# dcy_vca_v1_0_0.net
KiCad netlist of a schematic drawn in EAGLE
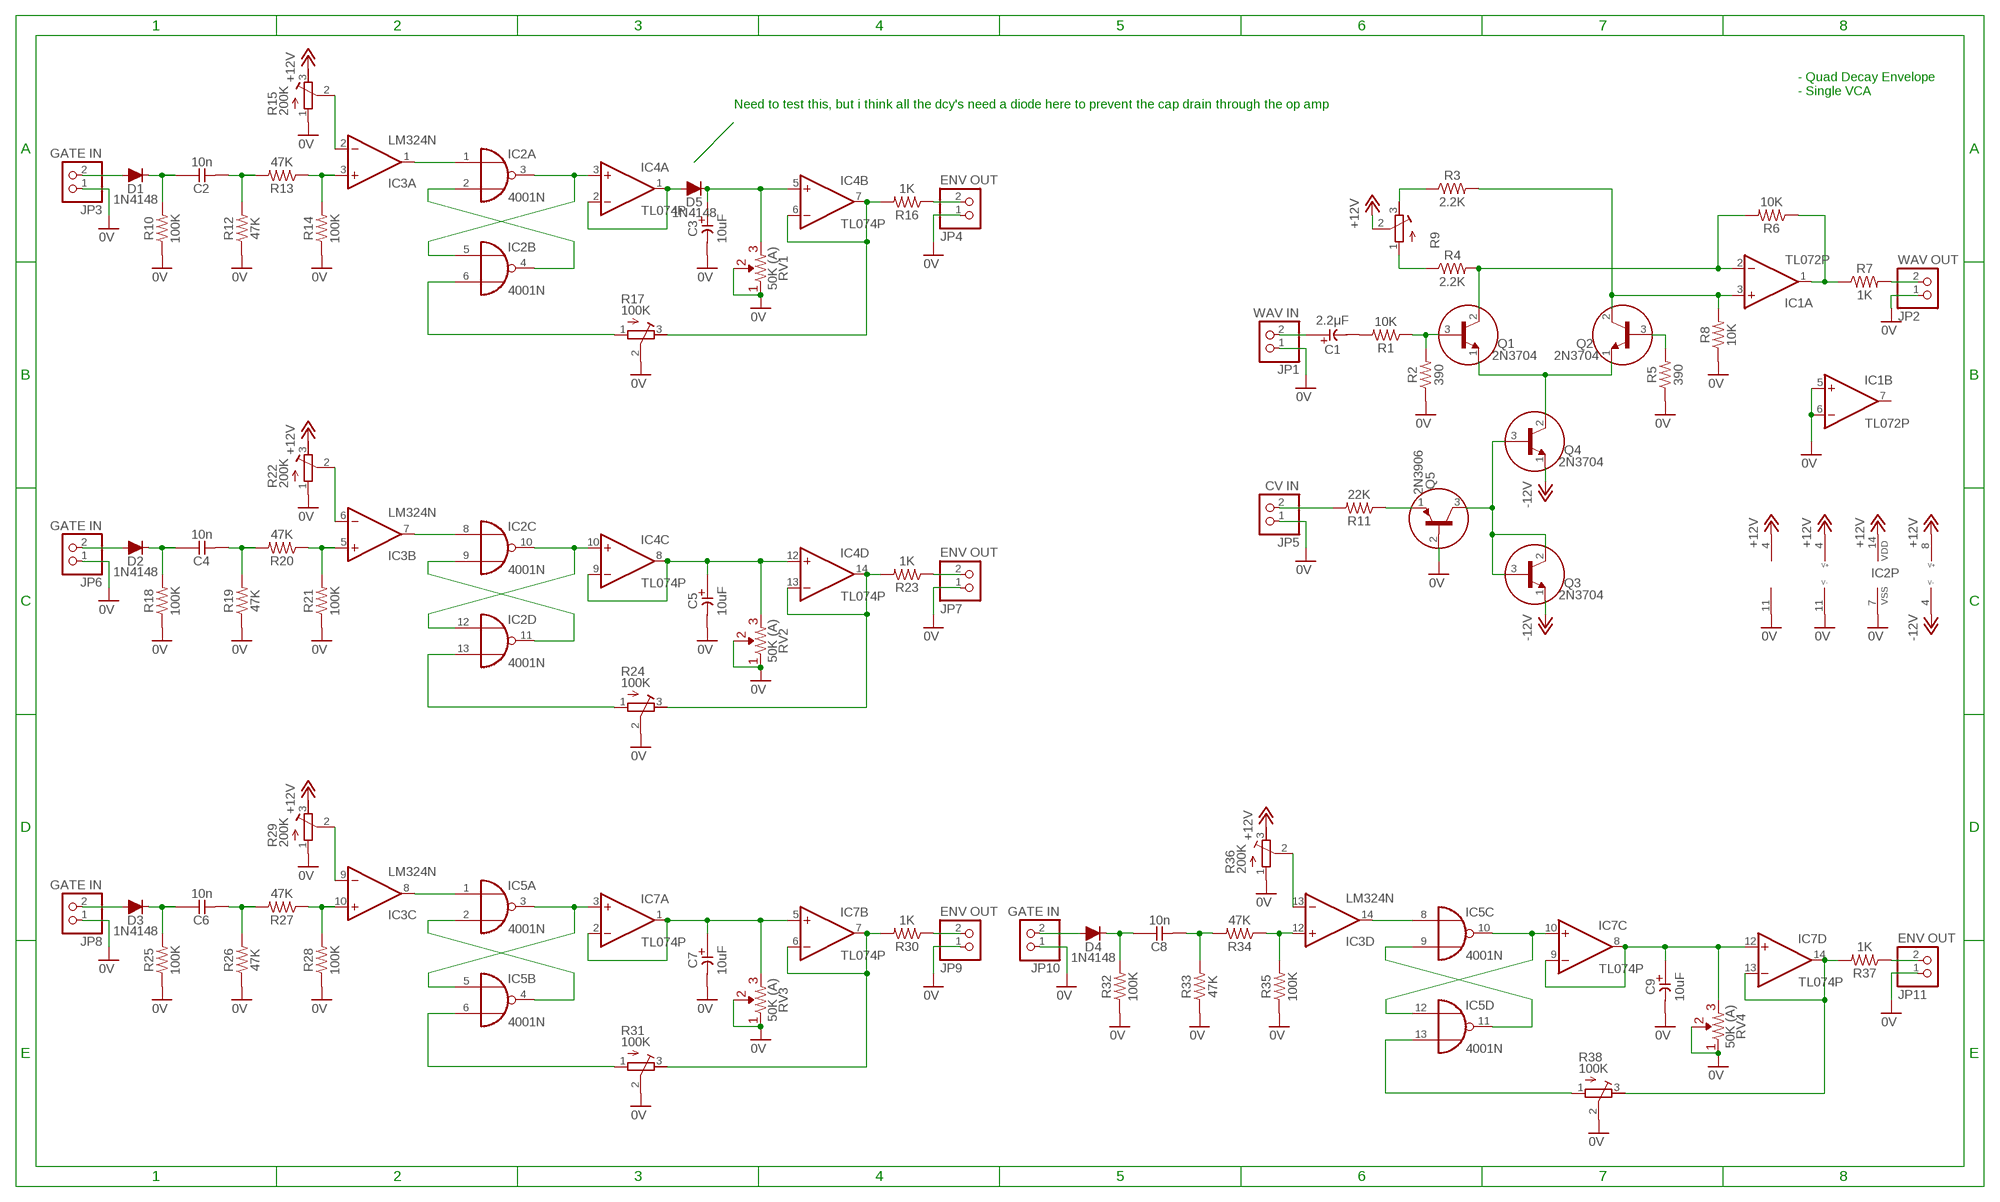
[diagram p0: schematic, sheet 1]

(export (version "E")
  (design (tool "Eeschema 10.0.6"))
  (components
    (comp (ref "C1")
      (value "2.2μF")
      (footprint "eagle-import:E2-5")
      (libsource (lib "eagle-import") (part "CE-USE2-5"))
    )
    (comp (ref "C2")
      (value "10n")
      (footprint "eagle-import:C025-024X044")
      (libsource (lib "eagle-import") (part "CC-US025-024X044"))
    )
    (comp (ref "C3")
      (value "10uF")
      (footprint "eagle-import:E2-5")
      (libsource (lib "eagle-import") (part "CE-USE2-5"))
    )
    (comp (ref "C4")
      (value "10n")
      (footprint "eagle-import:C025-024X044")
      (libsource (lib "eagle-import") (part "CC-US025-024X044"))
    )
    (comp (ref "C5")
      (value "10uF")
      (footprint "eagle-import:E2-5")
      (libsource (lib "eagle-import") (part "CE-USE2-5"))
    )
    (comp (ref "C6")
      (value "10n")
      (footprint "eagle-import:C025-024X044")
      (libsource (lib "eagle-import") (part "CC-US025-024X044"))
    )
    (comp (ref "C7")
      (value "10uF")
      (footprint "eagle-import:E2-5")
      (libsource (lib "eagle-import") (part "CE-USE2-5"))
    )
    (comp (ref "C8")
      (value "10n")
      (footprint "eagle-import:C025-024X044")
      (libsource (lib "eagle-import") (part "CC-US025-024X044"))
    )
    (comp (ref "C9")
      (value "10uF")
      (footprint "eagle-import:E2-5")
      (libsource (lib "eagle-import") (part "CE-USE2-5"))
    )
    (comp (ref "D1")
      (value "1N4148")
      (footprint "eagle-import:DO35-7")
      (libsource (lib "eagle-import") (part "1N4148"))
    )
    (comp (ref "D2")
      (value "1N4148")
      (footprint "eagle-import:DO35-7")
      (libsource (lib "eagle-import") (part "1N4148"))
    )
    (comp (ref "D3")
      (value "1N4148")
      (footprint "eagle-import:DO35-7")
      (libsource (lib "eagle-import") (part "1N4148"))
    )
    (comp (ref "D4")
      (value "1N4148")
      (footprint "eagle-import:DO35-7")
      (libsource (lib "eagle-import") (part "1N4148"))
    )
    (comp (ref "D5")
      (value "1N4148")
      (footprint "eagle-import:DO35-7")
      (libsource (lib "eagle-import") (part "1N4148"))
    )
    (comp (ref "IC1")
      (value "TL072P")
      (footprint "eagle-import:DIL08")
      (libsource (lib "eagle-import") (part "TL072P"))
    )
    (comp (ref "IC2")
      (value "4001N")
      (footprint "eagle-import:DIL14")
      (libsource (lib "eagle-import") (part "4001N"))
    )
    (comp (ref "IC3")
      (value "LM324N")
      (footprint "eagle-import:DIL14")
      (libsource (lib "eagle-import") (part "LM324N"))
    )
    (comp (ref "IC4")
      (value "TL074P")
      (footprint "eagle-import:DIL14")
      (libsource (lib "eagle-import") (part "TL074P"))
    )
    (comp (ref "IC5")
      (value "4001N")
      (footprint "eagle-import:DIL14")
      (libsource (lib "eagle-import") (part "4001N"))
    )
    (comp (ref "IC7")
      (value "TL074P")
      (footprint "eagle-import:DIL14")
      (libsource (lib "eagle-import") (part "TL074P"))
    )
    (comp (ref "JP1")
      (value "WAV IN")
      (footprint "eagle-import:1X02")
      (libsource (lib "eagle-import") (part "PINHD-1X2"))
    )
    (comp (ref "JP2")
      (value "WAV OUT")
      (footprint "eagle-import:1X02")
      (libsource (lib "eagle-import") (part "PINHD-1X2"))
    )
    (comp (ref "JP3")
      (value "GATE IN")
      (footprint "eagle-import:1X02")
      (libsource (lib "eagle-import") (part "PINHD-1X2"))
    )
    (comp (ref "JP4")
      (value "ENV OUT")
      (footprint "eagle-import:1X02")
      (libsource (lib "eagle-import") (part "PINHD-1X2"))
    )
    (comp (ref "JP5")
      (value "CV IN")
      (footprint "eagle-import:1X02")
      (libsource (lib "eagle-import") (part "PINHD-1X2"))
    )
    (comp (ref "JP6")
      (value "GATE IN")
      (footprint "eagle-import:1X02")
      (libsource (lib "eagle-import") (part "PINHD-1X2"))
    )
    (comp (ref "JP7")
      (value "ENV OUT")
      (footprint "eagle-import:1X02")
      (libsource (lib "eagle-import") (part "PINHD-1X2"))
    )
    (comp (ref "JP8")
      (value "GATE IN")
      (footprint "eagle-import:1X02")
      (libsource (lib "eagle-import") (part "PINHD-1X2"))
    )
    (comp (ref "JP9")
      (value "ENV OUT")
      (footprint "eagle-import:1X02")
      (libsource (lib "eagle-import") (part "PINHD-1X2"))
    )
    (comp (ref "JP10")
      (value "GATE IN")
      (footprint "eagle-import:1X02")
      (libsource (lib "eagle-import") (part "PINHD-1X2"))
    )
    (comp (ref "JP11")
      (value "ENV OUT")
      (footprint "eagle-import:1X02")
      (libsource (lib "eagle-import") (part "PINHD-1X2"))
    )
    (comp (ref "Q1")
      (value "2N3704")
      (footprint "eagle-import:TO92")
      (libsource (lib "eagle-import") (part "2N3704"))
    )
    (comp (ref "Q2")
      (value "2N3704")
      (footprint "eagle-import:TO92")
      (libsource (lib "eagle-import") (part "2N3704"))
    )
    (comp (ref "Q3")
      (value "2N3704")
      (footprint "eagle-import:TO92")
      (libsource (lib "eagle-import") (part "2N3704"))
    )
    (comp (ref "Q4")
      (value "2N3704")
      (footprint "eagle-import:TO92")
      (libsource (lib "eagle-import") (part "2N3704"))
    )
    (comp (ref "Q5")
      (value "2N3906")
      (footprint "eagle-import:TO92")
      (libsource (lib "eagle-import") (part "2N3906"))
    )
    (comp (ref "R1")
      (value "10K")
      (footprint "eagle-import:0309_10")
      (libsource (lib "eagle-import") (part "R0309/10"))
    )
    (comp (ref "R2")
      (value "390")
      (footprint "eagle-import:0309_10")
      (libsource (lib "eagle-import") (part "R0309/10"))
    )
    (comp (ref "R3")
      (value "2.2K")
      (footprint "eagle-import:0309_10")
      (libsource (lib "eagle-import") (part "R0309/10"))
    )
    (comp (ref "R4")
      (value "2.2K")
      (footprint "eagle-import:0309_10")
      (libsource (lib "eagle-import") (part "R0309/10"))
    )
    (comp (ref "R5")
      (value "390")
      (footprint "eagle-import:0309_10")
      (libsource (lib "eagle-import") (part "R0309/10"))
    )
    (comp (ref "R6")
      (value "10K")
      (footprint "eagle-import:0309_10")
      (libsource (lib "eagle-import") (part "R0309/10"))
    )
    (comp (ref "R7")
      (value "1K")
      (footprint "eagle-import:0309_10")
      (libsource (lib "eagle-import") (part "R0309/10"))
    )
    (comp (ref "R8")
      (value "10K")
      (footprint "eagle-import:0309_10")
      (libsource (lib "eagle-import") (part "R0309/10"))
    )
    (comp (ref "R9")
      (value "R-TRIMM3339P")
      (footprint "eagle-import:RTRIM3339P")
      (libsource (lib "eagle-import") (part "R-TRIMM3339P"))
    )
    (comp (ref "R10")
      (value "100K")
      (footprint "eagle-import:0309_10")
      (libsource (lib "eagle-import") (part "R0309/10"))
    )
    (comp (ref "R11")
      (value "22K")
      (footprint "eagle-import:0309_10")
      (libsource (lib "eagle-import") (part "R0309/10"))
    )
    (comp (ref "R12")
      (value "47K")
      (footprint "eagle-import:0309_10")
      (libsource (lib "eagle-import") (part "R0309/10"))
    )
    (comp (ref "R13")
      (value "47K")
      (footprint "eagle-import:0309_10")
      (libsource (lib "eagle-import") (part "R0309/10"))
    )
    (comp (ref "R14")
      (value "100K")
      (footprint "eagle-import:0309_10")
      (libsource (lib "eagle-import") (part "R0309/10"))
    )
    (comp (ref "R15")
      (value "200K")
      (footprint "eagle-import:RTRIM3339P")
      (libsource (lib "eagle-import") (part "R-TRIMM3339P"))
    )
    (comp (ref "R16")
      (value "1K")
      (footprint "eagle-import:0309_10")
      (libsource (lib "eagle-import") (part "R0309/10"))
    )
    (comp (ref "R17")
      (value "100K")
      (footprint "eagle-import:RTRIM3339P")
      (libsource (lib "eagle-import") (part "R-TRIMM3339P"))
    )
    (comp (ref "R18")
      (value "100K")
      (footprint "eagle-import:0309_10")
      (libsource (lib "eagle-import") (part "R0309/10"))
    )
    (comp (ref "R19")
      (value "47K")
      (footprint "eagle-import:0309_10")
      (libsource (lib "eagle-import") (part "R0309/10"))
    )
    (comp (ref "R20")
      (value "47K")
      (footprint "eagle-import:0309_10")
      (libsource (lib "eagle-import") (part "R0309/10"))
    )
    (comp (ref "R21")
      (value "100K")
      (footprint "eagle-import:0309_10")
      (libsource (lib "eagle-import") (part "R0309/10"))
    )
    (comp (ref "R22")
      (value "200K")
      (footprint "eagle-import:RTRIM3339P")
      (libsource (lib "eagle-import") (part "R-TRIMM3339P"))
    )
    (comp (ref "R23")
      (value "1K")
      (footprint "eagle-import:0309_10")
      (libsource (lib "eagle-import") (part "R0309/10"))
    )
    (comp (ref "R24")
      (value "100K")
      (footprint "eagle-import:RTRIM3339P")
      (libsource (lib "eagle-import") (part "R-TRIMM3339P"))
    )
    (comp (ref "R25")
      (value "100K")
      (footprint "eagle-import:0309_10")
      (libsource (lib "eagle-import") (part "R0309/10"))
    )
    (comp (ref "R26")
      (value "47K")
      (footprint "eagle-import:0309_10")
      (libsource (lib "eagle-import") (part "R0309/10"))
    )
    (comp (ref "R27")
      (value "47K")
      (footprint "eagle-import:0309_10")
      (libsource (lib "eagle-import") (part "R0309/10"))
    )
    (comp (ref "R28")
      (value "100K")
      (footprint "eagle-import:0309_10")
      (libsource (lib "eagle-import") (part "R0309/10"))
    )
    (comp (ref "R29")
      (value "200K")
      (footprint "eagle-import:RTRIM3339P")
      (libsource (lib "eagle-import") (part "R-TRIMM3339P"))
    )
    (comp (ref "R30")
      (value "1K")
      (footprint "eagle-import:0309_10")
      (libsource (lib "eagle-import") (part "R0309/10"))
    )
    (comp (ref "R31")
      (value "100K")
      (footprint "eagle-import:RTRIM3339P")
      (libsource (lib "eagle-import") (part "R-TRIMM3339P"))
    )
    (comp (ref "R32")
      (value "100K")
      (footprint "eagle-import:0309_10")
      (libsource (lib "eagle-import") (part "R0309/10"))
    )
    (comp (ref "R33")
      (value "47K")
      (footprint "eagle-import:0309_10")
      (libsource (lib "eagle-import") (part "R0309/10"))
    )
    (comp (ref "R34")
      (value "47K")
      (footprint "eagle-import:0309_10")
      (libsource (lib "eagle-import") (part "R0309/10"))
    )
    (comp (ref "R35")
      (value "100K")
      (footprint "eagle-import:0309_10")
      (libsource (lib "eagle-import") (part "R0309/10"))
    )
    (comp (ref "R36")
      (value "200K")
      (footprint "eagle-import:RTRIM3339P")
      (libsource (lib "eagle-import") (part "R-TRIMM3339P"))
    )
    (comp (ref "R37")
      (value "1K")
      (footprint "eagle-import:0309_10")
      (libsource (lib "eagle-import") (part "R0309/10"))
    )
    (comp (ref "R38")
      (value "100K")
      (footprint "eagle-import:RTRIM3339P")
      (libsource (lib "eagle-import") (part "R-TRIMM3339P"))
    )
    (comp (ref "RV1")
      (value "50K (A)")
      (footprint "eagle-import:R-VAR")
      (libsource (lib "eagle-import") (part "R-VAR"))
    )
    (comp (ref "RV2")
      (value "50K (A)")
      (footprint "eagle-import:R-VAR")
      (libsource (lib "eagle-import") (part "R-VAR"))
    )
    (comp (ref "RV3")
      (value "50K (A)")
      (footprint "eagle-import:R-VAR")
      (libsource (lib "eagle-import") (part "R-VAR"))
    )
    (comp (ref "RV4")
      (value "50K (A)")
      (footprint "eagle-import:R-VAR")
      (libsource (lib "eagle-import") (part "R-VAR"))
    )
  )
  (nets
    (net (code "1") (name "+12V") (class "Default")
      (node (ref "IC1") (pin "8") (pinfunction "V+_8") (pintype "power_in"))
      (node (ref "IC2") (pin "14") (pinfunction "VDD_14") (pintype "power_in"))
      (node (ref "IC3") (pin "4") (pinfunction "V+_4") (pintype "power_in"))
      (node (ref "IC4") (pin "4") (pinfunction "V+_4") (pintype "power_in"))
      (node (ref "R15") (pin "3") (pinfunction "E_3") (pintype "passive"))
      (node (ref "R22") (pin "3") (pinfunction "E_3") (pintype "passive"))
      (node (ref "R29") (pin "3") (pinfunction "E_3") (pintype "passive"))
      (node (ref "R36") (pin "3") (pinfunction "E_3") (pintype "passive"))
      (node (ref "R9") (pin "2") (pinfunction "S_2") (pintype "passive"))
    )
    (net (code "2") (name "-12V") (class "Default")
      (node (ref "IC1") (pin "4") (pinfunction "V-_4") (pintype "power_in"))
      (node (ref "Q3") (pin "1") (pinfunction "E_1") (pintype "passive"))
      (node (ref "Q4") (pin "1") (pinfunction "E_1") (pintype "passive"))
    )
    (net (code "3") (name "0V") (class "Default")
      (node (ref "C3") (pin "-") (pinfunction "-_-") (pintype "passive"))
      (node (ref "C5") (pin "-") (pinfunction "-_-") (pintype "passive"))
      (node (ref "C7") (pin "-") (pinfunction "-_-") (pintype "passive"))
      (node (ref "C9") (pin "-") (pinfunction "-_-") (pintype "passive"))
      (node (ref "IC1") (pin "5") (pinfunction "+IN_5") (pintype "input"))
      (node (ref "IC1") (pin "6") (pinfunction "-IN_6") (pintype "input"))
      (node (ref "IC2") (pin "7") (pinfunction "VSS_7") (pintype "power_in"))
      (node (ref "IC3") (pin "11") (pinfunction "V-_11") (pintype "power_in"))
      (node (ref "IC4") (pin "11") (pinfunction "V-_11") (pintype "power_in"))
      (node (ref "JP1") (pin "1") (pinfunction "1_1") (pintype "passive"))
      (node (ref "JP10") (pin "1") (pinfunction "1_1") (pintype "passive"))
      (node (ref "JP11") (pin "1") (pinfunction "1_1") (pintype "passive"))
      (node (ref "JP2") (pin "1") (pinfunction "1_1") (pintype "passive"))
      (node (ref "JP3") (pin "1") (pinfunction "1_1") (pintype "passive"))
      (node (ref "JP4") (pin "1") (pinfunction "1_1") (pintype "passive"))
      (node (ref "JP5") (pin "1") (pinfunction "1_1") (pintype "passive"))
      (node (ref "JP6") (pin "1") (pinfunction "1_1") (pintype "passive"))
      (node (ref "JP7") (pin "1") (pinfunction "1_1") (pintype "passive"))
      (node (ref "JP8") (pin "1") (pinfunction "1_1") (pintype "passive"))
      (node (ref "JP9") (pin "1") (pinfunction "1_1") (pintype "passive"))
      (node (ref "Q5") (pin "2") (pinfunction "B_2") (pintype "passive"))
      (node (ref "R10") (pin "1") (pinfunction "1_1") (pintype "passive"))
      (node (ref "R12") (pin "1") (pinfunction "1_1") (pintype "passive"))
      (node (ref "R14") (pin "1") (pinfunction "1_1") (pintype "passive"))
      (node (ref "R15") (pin "1") (pinfunction "A_1") (pintype "passive"))
      (node (ref "R17") (pin "2") (pinfunction "S_2") (pintype "passive"))
      (node (ref "R18") (pin "1") (pinfunction "1_1") (pintype "passive"))
      (node (ref "R19") (pin "1") (pinfunction "1_1") (pintype "passive"))
      (node (ref "R2") (pin "1") (pinfunction "1_1") (pintype "passive"))
      (node (ref "R21") (pin "1") (pinfunction "1_1") (pintype "passive"))
      (node (ref "R22") (pin "1") (pinfunction "A_1") (pintype "passive"))
      (node (ref "R24") (pin "2") (pinfunction "S_2") (pintype "passive"))
      (node (ref "R25") (pin "1") (pinfunction "1_1") (pintype "passive"))
      (node (ref "R26") (pin "1") (pinfunction "1_1") (pintype "passive"))
      (node (ref "R28") (pin "1") (pinfunction "1_1") (pintype "passive"))
      (node (ref "R29") (pin "1") (pinfunction "A_1") (pintype "passive"))
      (node (ref "R31") (pin "2") (pinfunction "S_2") (pintype "passive"))
      (node (ref "R32") (pin "1") (pinfunction "1_1") (pintype "passive"))
      (node (ref "R33") (pin "1") (pinfunction "1_1") (pintype "passive"))
      (node (ref "R35") (pin "1") (pinfunction "1_1") (pintype "passive"))
      (node (ref "R36") (pin "1") (pinfunction "A_1") (pintype "passive"))
      (node (ref "R38") (pin "2") (pinfunction "S_2") (pintype "passive"))
      (node (ref "R5") (pin "1") (pinfunction "1_1") (pintype "passive"))
      (node (ref "R8") (pin "1") (pinfunction "1_1") (pintype "passive"))
      (node (ref "RV1") (pin "R1") (pinfunction "1_R1") (pintype "passive"))
      (node (ref "RV1") (pin "VAR") (pinfunction "P$1_VAR") (pintype "passive"))
      (node (ref "RV2") (pin "R1") (pinfunction "1_R1") (pintype "passive"))
      (node (ref "RV2") (pin "VAR") (pinfunction "P$1_VAR") (pintype "passive"))
      (node (ref "RV3") (pin "R1") (pinfunction "1_R1") (pintype "passive"))
      (node (ref "RV3") (pin "VAR") (pinfunction "P$1_VAR") (pintype "passive"))
      (node (ref "RV4") (pin "R1") (pinfunction "1_R1") (pintype "passive"))
      (node (ref "RV4") (pin "VAR") (pinfunction "P$1_VAR") (pintype "passive"))
    )
    (net (code "4") (name "Net-(C1-Pad+)") (class "Default")
      (node (ref "C1") (pin "+") (pinfunction "+_+") (pintype "passive"))
      (node (ref "JP1") (pin "2") (pinfunction "2_2") (pintype "passive"))
    )
    (net (code "5") (name "Net-(C1-Pad-)") (class "Default")
      (node (ref "C1") (pin "-") (pinfunction "-_-") (pintype "passive"))
      (node (ref "R1") (pin "2") (pinfunction "2_2") (pintype "passive"))
    )
    (net (code "6") (name "Net-(C2-Pad1)") (class "Default")
      (node (ref "C2") (pin "1") (pinfunction "1_1") (pintype "passive"))
      (node (ref "D1") (pin "C") (pinfunction "C_C") (pintype "passive"))
      (node (ref "R10") (pin "2") (pinfunction "2_2") (pintype "passive"))
    )
    (net (code "7") (name "Net-(C2-Pad2)") (class "Default")
      (node (ref "C2") (pin "2") (pinfunction "2_2") (pintype "passive"))
      (node (ref "R12") (pin "2") (pinfunction "2_2") (pintype "passive"))
      (node (ref "R13") (pin "2") (pinfunction "2_2") (pintype "passive"))
    )
    (net (code "8") (name "Net-(C4-Pad1)") (class "Default")
      (node (ref "C4") (pin "1") (pinfunction "1_1") (pintype "passive"))
      (node (ref "D2") (pin "C") (pinfunction "C_C") (pintype "passive"))
      (node (ref "R18") (pin "2") (pinfunction "2_2") (pintype "passive"))
    )
    (net (code "9") (name "Net-(C4-Pad2)") (class "Default")
      (node (ref "C4") (pin "2") (pinfunction "2_2") (pintype "passive"))
      (node (ref "R19") (pin "2") (pinfunction "2_2") (pintype "passive"))
      (node (ref "R20") (pin "2") (pinfunction "2_2") (pintype "passive"))
    )
    (net (code "10") (name "Net-(C6-Pad1)") (class "Default")
      (node (ref "C6") (pin "1") (pinfunction "1_1") (pintype "passive"))
      (node (ref "D3") (pin "C") (pinfunction "C_C") (pintype "passive"))
      (node (ref "R25") (pin "2") (pinfunction "2_2") (pintype "passive"))
    )
    (net (code "11") (name "Net-(C6-Pad2)") (class "Default")
      (node (ref "C6") (pin "2") (pinfunction "2_2") (pintype "passive"))
      (node (ref "R26") (pin "2") (pinfunction "2_2") (pintype "passive"))
      (node (ref "R27") (pin "2") (pinfunction "2_2") (pintype "passive"))
    )
    (net (code "12") (name "Net-(C8-Pad1)") (class "Default")
      (node (ref "C8") (pin "1") (pinfunction "1_1") (pintype "passive"))
      (node (ref "D4") (pin "C") (pinfunction "C_C") (pintype "passive"))
      (node (ref "R32") (pin "2") (pinfunction "2_2") (pintype "passive"))
    )
    (net (code "13") (name "Net-(C8-Pad2)") (class "Default")
      (node (ref "C8") (pin "2") (pinfunction "2_2") (pintype "passive"))
      (node (ref "R33") (pin "2") (pinfunction "2_2") (pintype "passive"))
      (node (ref "R34") (pin "2") (pinfunction "2_2") (pintype "passive"))
    )
    (net (code "14") (name "Net-(D1-PadA)") (class "Default")
      (node (ref "D1") (pin "A") (pinfunction "A_A") (pintype "passive"))
      (node (ref "JP3") (pin "2") (pinfunction "2_2") (pintype "passive"))
    )
    (net (code "15") (name "Net-(D2-PadA)") (class "Default")
      (node (ref "D2") (pin "A") (pinfunction "A_A") (pintype "passive"))
      (node (ref "JP6") (pin "2") (pinfunction "2_2") (pintype "passive"))
    )
    (net (code "16") (name "Net-(D3-PadA)") (class "Default")
      (node (ref "D3") (pin "A") (pinfunction "A_A") (pintype "passive"))
      (node (ref "JP8") (pin "2") (pinfunction "2_2") (pintype "passive"))
    )
    (net (code "17") (name "Net-(D4-PadA)") (class "Default")
      (node (ref "D4") (pin "A") (pinfunction "A_A") (pintype "passive"))
      (node (ref "JP10") (pin "2") (pinfunction "2_2") (pintype "passive"))
    )
    (net (code "18") (name "Net-(IC1A-+IN)") (class "Default")
      (node (ref "IC1") (pin "3") (pinfunction "+IN_3") (pintype "input"))
      (node (ref "Q2") (pin "2") (pinfunction "C_2") (pintype "passive"))
      (node (ref "R3") (pin "2") (pinfunction "2_2") (pintype "passive"))
      (node (ref "R8") (pin "2") (pinfunction "2_2") (pintype "passive"))
    )
    (net (code "19") (name "Net-(IC1A--IN)") (class "Default")
      (node (ref "IC1") (pin "2") (pinfunction "-IN_2") (pintype "input"))
      (node (ref "Q1") (pin "2") (pinfunction "C_2") (pintype "passive"))
      (node (ref "R4") (pin "2") (pinfunction "2_2") (pintype "passive"))
      (node (ref "R6") (pin "2") (pinfunction "2_2") (pintype "passive"))
    )
    (net (code "20") (name "Net-(IC1A-OUT)") (class "Default")
      (node (ref "IC1") (pin "1") (pinfunction "OUT_1") (pintype "output"))
      (node (ref "R6") (pin "1") (pinfunction "1_1") (pintype "passive"))
      (node (ref "R7") (pin "1") (pinfunction "1_1") (pintype "passive"))
    )
    (net (code "21") (name "Net-(IC2A-I0)") (class "Default")
      (node (ref "IC2") (pin "1") (pinfunction "I0_1") (pintype "input"))
      (node (ref "IC3") (pin "1") (pinfunction "OUT_1") (pintype "output"))
    )
    (net (code "22") (name "Net-(IC2A-I1)") (class "Default")
      (node (ref "IC2") (pin "2") (pinfunction "I1_2") (pintype "input"))
      (node (ref "IC2") (pin "4") (pinfunction "O_4") (pintype "output"))
    )
    (net (code "23") (name "Net-(IC2A-O)") (class "Default")
      (node (ref "IC2") (pin "3") (pinfunction "O_3") (pintype "output"))
      (node (ref "IC2") (pin "5") (pinfunction "I0_5") (pintype "input"))
      (node (ref "IC4") (pin "3") (pinfunction "+IN_3") (pintype "input"))
    )
    (net (code "24") (name "Net-(IC2B-I1)") (class "Default")
      (node (ref "IC2") (pin "6") (pinfunction "I1_6") (pintype "input"))
      (node (ref "R17") (pin "1") (pinfunction "A_1") (pintype "passive"))
    )
    (net (code "25") (name "Net-(IC2C-I0)") (class "Default")
      (node (ref "IC2") (pin "8") (pinfunction "I0_8") (pintype "input"))
      (node (ref "IC3") (pin "7") (pinfunction "OUT_7") (pintype "output"))
    )
    (net (code "26") (name "Net-(IC2C-I1)") (class "Default")
      (node (ref "IC2") (pin "11") (pinfunction "O_11") (pintype "output"))
      (node (ref "IC2") (pin "9") (pinfunction "I1_9") (pintype "input"))
    )
    (net (code "27") (name "Net-(IC2C-O)") (class "Default")
      (node (ref "IC2") (pin "10") (pinfunction "O_10") (pintype "output"))
      (node (ref "IC2") (pin "12") (pinfunction "I0_12") (pintype "input"))
      (node (ref "IC4") (pin "10") (pinfunction "+IN_10") (pintype "input"))
    )
    (net (code "28") (name "Net-(IC2D-I1)") (class "Default")
      (node (ref "IC2") (pin "13") (pinfunction "I1_13") (pintype "input"))
      (node (ref "R24") (pin "1") (pinfunction "A_1") (pintype "passive"))
    )
    (net (code "29") (name "Net-(IC3A-+IN)") (class "Default")
      (node (ref "IC3") (pin "3") (pinfunction "+IN_3") (pintype "input"))
      (node (ref "R13") (pin "1") (pinfunction "1_1") (pintype "passive"))
      (node (ref "R14") (pin "2") (pinfunction "2_2") (pintype "passive"))
    )
    (net (code "30") (name "Net-(IC3A--IN)") (class "Default")
      (node (ref "IC3") (pin "2") (pinfunction "-IN_2") (pintype "input"))
      (node (ref "R15") (pin "2") (pinfunction "S_2") (pintype "passive"))
    )
    (net (code "31") (name "Net-(IC3B-+IN)") (class "Default")
      (node (ref "IC3") (pin "5") (pinfunction "+IN_5") (pintype "input"))
      (node (ref "R20") (pin "1") (pinfunction "1_1") (pintype "passive"))
      (node (ref "R21") (pin "2") (pinfunction "2_2") (pintype "passive"))
    )
    (net (code "32") (name "Net-(IC3B--IN)") (class "Default")
      (node (ref "IC3") (pin "6") (pinfunction "-IN_6") (pintype "input"))
      (node (ref "R22") (pin "2") (pinfunction "S_2") (pintype "passive"))
    )
    (net (code "33") (name "Net-(IC3C-+IN)") (class "Default")
      (node (ref "IC3") (pin "10") (pinfunction "+IN_10") (pintype "input"))
      (node (ref "R27") (pin "1") (pinfunction "1_1") (pintype "passive"))
      (node (ref "R28") (pin "2") (pinfunction "2_2") (pintype "passive"))
    )
    (net (code "34") (name "Net-(IC3C--IN)") (class "Default")
      (node (ref "IC3") (pin "9") (pinfunction "-IN_9") (pintype "input"))
      (node (ref "R29") (pin "2") (pinfunction "S_2") (pintype "passive"))
    )
    (net (code "35") (name "Net-(IC3C-OUT)") (class "Default")
      (node (ref "IC3") (pin "8") (pinfunction "OUT_8") (pintype "output"))
      (node (ref "IC5") (pin "1") (pinfunction "I0_1") (pintype "input"))
    )
    (net (code "36") (name "Net-(IC3D-+IN)") (class "Default")
      (node (ref "IC3") (pin "12") (pinfunction "+IN_12") (pintype "input"))
      (node (ref "R34") (pin "1") (pinfunction "1_1") (pintype "passive"))
      (node (ref "R35") (pin "2") (pinfunction "2_2") (pintype "passive"))
    )
    (net (code "37") (name "Net-(IC3D--IN)") (class "Default")
      (node (ref "IC3") (pin "13") (pinfunction "-IN_13") (pintype "input"))
      (node (ref "R36") (pin "2") (pinfunction "S_2") (pintype "passive"))
    )
    (net (code "38") (name "Net-(IC3D-OUT)") (class "Default")
      (node (ref "IC3") (pin "14") (pinfunction "OUT_14") (pintype "output"))
      (node (ref "IC5") (pin "8") (pinfunction "I0_8") (pintype "input"))
    )
    (net (code "39") (name "Net-(IC4A--IN)") (class "Default")
      (node (ref "D5") (pin "A") (pinfunction "A_A") (pintype "passive"))
      (node (ref "IC4") (pin "1") (pinfunction "OUT_1") (pintype "output"))
      (node (ref "IC4") (pin "2") (pinfunction "-IN_2") (pintype "input"))
    )
    (net (code "40") (name "Net-(IC4B-+IN)") (class "Default")
      (node (ref "C3") (pin "+") (pinfunction "+_+") (pintype "passive"))
      (node (ref "D5") (pin "C") (pinfunction "C_C") (pintype "passive"))
      (node (ref "IC4") (pin "5") (pinfunction "+IN_5") (pintype "input"))
      (node (ref "RV1") (pin "R2") (pinfunction "2_R2") (pintype "passive"))
    )
    (net (code "41") (name "Net-(IC4B--IN)") (class "Default")
      (node (ref "IC4") (pin "6") (pinfunction "-IN_6") (pintype "input"))
      (node (ref "IC4") (pin "7") (pinfunction "OUT_7") (pintype "output"))
      (node (ref "R16") (pin "2") (pinfunction "2_2") (pintype "passive"))
      (node (ref "R17") (pin "3") (pinfunction "E_3") (pintype "passive"))
    )
    (net (code "42") (name "Net-(IC4C--IN)") (class "Default")
      (node (ref "C5") (pin "+") (pinfunction "+_+") (pintype "passive"))
      (node (ref "IC4") (pin "12") (pinfunction "+IN_12") (pintype "input"))
      (node (ref "IC4") (pin "8") (pinfunction "OUT_8") (pintype "output"))
      (node (ref "IC4") (pin "9") (pinfunction "-IN_9") (pintype "input"))
      (node (ref "RV2") (pin "R2") (pinfunction "2_R2") (pintype "passive"))
    )
    (net (code "43") (name "Net-(IC4D--IN)") (class "Default")
      (node (ref "IC4") (pin "13") (pinfunction "-IN_13") (pintype "input"))
      (node (ref "IC4") (pin "14") (pinfunction "OUT_14") (pintype "output"))
      (node (ref "R23") (pin "2") (pinfunction "2_2") (pintype "passive"))
      (node (ref "R24") (pin "3") (pinfunction "E_3") (pintype "passive"))
    )
    (net (code "44") (name "Net-(IC5A-I1)") (class "Default")
      (node (ref "IC5") (pin "2") (pinfunction "I1_2") (pintype "input"))
      (node (ref "IC5") (pin "4") (pinfunction "O_4") (pintype "output"))
    )
    (net (code "45") (name "Net-(IC5A-O)") (class "Default")
      (node (ref "IC5") (pin "3") (pinfunction "O_3") (pintype "output"))
      (node (ref "IC5") (pin "5") (pinfunction "I0_5") (pintype "input"))
      (node (ref "IC7") (pin "3") (pinfunction "+IN_3") (pintype "input"))
    )
    (net (code "46") (name "Net-(IC5B-I1)") (class "Default")
      (node (ref "IC5") (pin "6") (pinfunction "I1_6") (pintype "input"))
      (node (ref "R31") (pin "1") (pinfunction "A_1") (pintype "passive"))
    )
    (net (code "47") (name "Net-(IC5C-I1)") (class "Default")
      (node (ref "IC5") (pin "11") (pinfunction "O_11") (pintype "output"))
      (node (ref "IC5") (pin "9") (pinfunction "I1_9") (pintype "input"))
    )
    (net (code "48") (name "Net-(IC5C-O)") (class "Default")
      (node (ref "IC5") (pin "10") (pinfunction "O_10") (pintype "output"))
      (node (ref "IC5") (pin "12") (pinfunction "I0_12") (pintype "input"))
      (node (ref "IC7") (pin "10") (pinfunction "+IN_10") (pintype "input"))
    )
    (net (code "49") (name "Net-(IC5D-I1)") (class "Default")
      (node (ref "IC5") (pin "13") (pinfunction "I1_13") (pintype "input"))
      (node (ref "R38") (pin "1") (pinfunction "A_1") (pintype "passive"))
    )
    (net (code "50") (name "Net-(IC7A--IN)") (class "Default")
      (node (ref "C7") (pin "+") (pinfunction "+_+") (pintype "passive"))
      (node (ref "IC7") (pin "1") (pinfunction "OUT_1") (pintype "output"))
      (node (ref "IC7") (pin "2") (pinfunction "-IN_2") (pintype "input"))
      (node (ref "IC7") (pin "5") (pinfunction "+IN_5") (pintype "input"))
      (node (ref "RV3") (pin "R2") (pinfunction "2_R2") (pintype "passive"))
    )
    (net (code "51") (name "Net-(IC7B--IN)") (class "Default")
      (node (ref "IC7") (pin "6") (pinfunction "-IN_6") (pintype "input"))
      (node (ref "IC7") (pin "7") (pinfunction "OUT_7") (pintype "output"))
      (node (ref "R30") (pin "2") (pinfunction "2_2") (pintype "passive"))
      (node (ref "R31") (pin "3") (pinfunction "E_3") (pintype "passive"))
    )
    (net (code "52") (name "Net-(IC7C--IN)") (class "Default")
      (node (ref "C9") (pin "+") (pinfunction "+_+") (pintype "passive"))
      (node (ref "IC7") (pin "12") (pinfunction "+IN_12") (pintype "input"))
      (node (ref "IC7") (pin "8") (pinfunction "OUT_8") (pintype "output"))
      (node (ref "IC7") (pin "9") (pinfunction "-IN_9") (pintype "input"))
      (node (ref "RV4") (pin "R2") (pinfunction "2_R2") (pintype "passive"))
    )
    (net (code "53") (name "Net-(IC7D--IN)") (class "Default")
      (node (ref "IC7") (pin "13") (pinfunction "-IN_13") (pintype "input"))
      (node (ref "IC7") (pin "14") (pinfunction "OUT_14") (pintype "output"))
      (node (ref "R37") (pin "2") (pinfunction "2_2") (pintype "passive"))
      (node (ref "R38") (pin "3") (pinfunction "E_3") (pintype "passive"))
    )
    (net (code "54") (name "Net-(JP2-Pad2)") (class "Default")
      (node (ref "JP2") (pin "2") (pinfunction "2_2") (pintype "passive"))
      (node (ref "R7") (pin "2") (pinfunction "2_2") (pintype "passive"))
    )
    (net (code "55") (name "Net-(JP4-Pad2)") (class "Default")
      (node (ref "JP4") (pin "2") (pinfunction "2_2") (pintype "passive"))
      (node (ref "R16") (pin "1") (pinfunction "1_1") (pintype "passive"))
    )
    (net (code "56") (name "Net-(JP5-Pad2)") (class "Default")
      (node (ref "JP5") (pin "2") (pinfunction "2_2") (pintype "passive"))
      (node (ref "R11") (pin "2") (pinfunction "2_2") (pintype "passive"))
    )
    (net (code "57") (name "Net-(JP7-Pad2)") (class "Default")
      (node (ref "JP7") (pin "2") (pinfunction "2_2") (pintype "passive"))
      (node (ref "R23") (pin "1") (pinfunction "1_1") (pintype "passive"))
    )
    (net (code "58") (name "Net-(JP9-Pad2)") (class "Default")
      (node (ref "JP9") (pin "2") (pinfunction "2_2") (pintype "passive"))
      (node (ref "R30") (pin "1") (pinfunction "1_1") (pintype "passive"))
    )
    (net (code "59") (name "Net-(JP11-Pad2)") (class "Default")
      (node (ref "JP11") (pin "2") (pinfunction "2_2") (pintype "passive"))
      (node (ref "R37") (pin "1") (pinfunction "1_1") (pintype "passive"))
    )
    (net (code "60") (name "Net-(Q1-B)") (class "Default")
      (node (ref "Q1") (pin "3") (pinfunction "B_3") (pintype "passive"))
      (node (ref "R1") (pin "1") (pinfunction "1_1") (pintype "passive"))
      (node (ref "R2") (pin "2") (pinfunction "2_2") (pintype "passive"))
    )
    (net (code "61") (name "Net-(Q1-E)") (class "Default")
      (node (ref "Q1") (pin "1") (pinfunction "E_1") (pintype "passive"))
      (node (ref "Q2") (pin "1") (pinfunction "E_1") (pintype "passive"))
      (node (ref "Q4") (pin "2") (pinfunction "C_2") (pintype "passive"))
    )
    (net (code "62") (name "Net-(Q2-B)") (class "Default")
      (node (ref "Q2") (pin "3") (pinfunction "B_3") (pintype "passive"))
      (node (ref "R5") (pin "2") (pinfunction "2_2") (pintype "passive"))
    )
    (net (code "63") (name "Net-(Q3-B)") (class "Default")
      (node (ref "Q3") (pin "2") (pinfunction "C_2") (pintype "passive"))
      (node (ref "Q3") (pin "3") (pinfunction "B_3") (pintype "passive"))
      (node (ref "Q4") (pin "3") (pinfunction "B_3") (pintype "passive"))
      (node (ref "Q5") (pin "3") (pinfunction "C_3") (pintype "passive"))
    )
    (net (code "64") (name "Net-(Q5-E)") (class "Default")
      (node (ref "Q5") (pin "1") (pinfunction "E_1") (pintype "passive"))
      (node (ref "R11") (pin "1") (pinfunction "1_1") (pintype "passive"))
    )
    (net (code "65") (name "Net-(R9-A)") (class "Default")
      (node (ref "R4") (pin "1") (pinfunction "1_1") (pintype "passive"))
      (node (ref "R9") (pin "1") (pinfunction "A_1") (pintype "passive"))
    )
    (net (code "66") (name "Net-(R9-E)") (class "Default")
      (node (ref "R3") (pin "1") (pinfunction "1_1") (pintype "passive"))
      (node (ref "R9") (pin "3") (pinfunction "E_3") (pintype "passive"))
    )
    (net (code "67") (name "unconnected-(IC1B-OUT-Pad7)") (class "Default")
      (node (ref "IC1") (pin "7") (pinfunction "OUT_7") (pintype "output"))
    )
  )
)
